# EE-Workshop.net
KiCad netlist of a schematic drawn in EAGLE
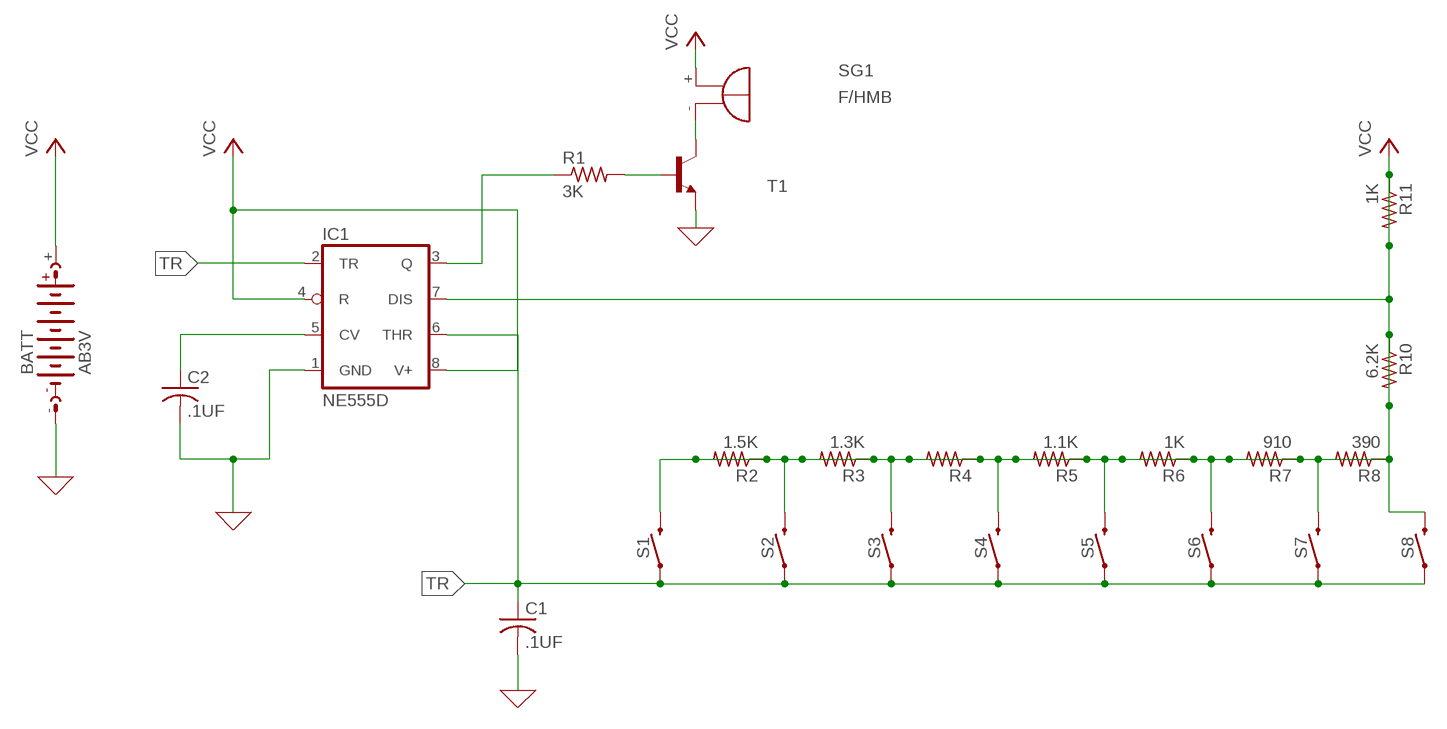
[diagram p0: schematic, sheet 1]

(export (version "E")
  (design (tool "Eeschema 10.0.6"))
  (components
    (comp (ref "BATT")
      (value "AB3V")
      (footprint "eagle-import:AB9V")
      (libsource (lib "eagle-import") (part "AB9V"))
    )
    (comp (ref "C1")
      (value ".1UF")
      (footprint "eagle-import:C0805")
      (libsource (lib "eagle-import") (part "C-USC0805"))
    )
    (comp (ref "C2")
      (value ".1UF")
      (footprint "eagle-import:C0805")
      (libsource (lib "eagle-import") (part "C-USC0805"))
    )
    (comp (ref "IC1")
      (value "NE555D")
      (footprint "eagle-import:SO08")
      (libsource (lib "eagle-import") (part "555DNE"))
    )
    (comp (ref "R1")
      (value "3K")
      (footprint "eagle-import:R0805")
      (libsource (lib "eagle-import") (part "R-US_R0805"))
    )
    (comp (ref "R2")
      (value "1.5K")
      (footprint "eagle-import:R0805")
      (libsource (lib "eagle-import") (part "R-US_R0805"))
    )
    (comp (ref "R3")
      (value "1.3K")
      (footprint "eagle-import:R0805")
      (libsource (lib "eagle-import") (part "R-US_R0805"))
    )
    (comp (ref "R4")
      (value "R-US_R0805")
      (footprint "eagle-import:R0805")
      (libsource (lib "eagle-import") (part "R-US_R0805"))
    )
    (comp (ref "R5")
      (value "1.1K")
      (footprint "eagle-import:R0805")
      (libsource (lib "eagle-import") (part "R-US_R0805"))
    )
    (comp (ref "R6")
      (value "1K")
      (footprint "eagle-import:R0805")
      (libsource (lib "eagle-import") (part "R-US_R0805"))
    )
    (comp (ref "R7")
      (value "910")
      (footprint "eagle-import:R0805")
      (libsource (lib "eagle-import") (part "R-US_R0805"))
    )
    (comp (ref "R8")
      (value "390")
      (footprint "eagle-import:R0805")
      (libsource (lib "eagle-import") (part "R-US_R0805"))
    )
    (comp (ref "R10")
      (value "6.2K")
      (footprint "eagle-import:R0805")
      (libsource (lib "eagle-import") (part "R-US_R0805"))
    )
    (comp (ref "R11")
      (value "1K")
      (footprint "eagle-import:R0805")
      (libsource (lib "eagle-import") (part "R-US_R0805"))
    )
    (comp (ref "S1")
      (value "MOMENTARY-SWITCH-SPST-SMD-6.2MM-TALL")
      (footprint "eagle-import:TACTILE_SWITCH_SMD_6.2MM_TALL")
      (libsource (lib "eagle-import") (part "MOMENTARY-SWITCH-SPST-SMD-6.2MM-TALL"))
    )
    (comp (ref "S2")
      (value "MOMENTARY-SWITCH-SPST-SMD-6.2MM-TALL")
      (footprint "eagle-import:TACTILE_SWITCH_SMD_6.2MM_TALL")
      (libsource (lib "eagle-import") (part "MOMENTARY-SWITCH-SPST-SMD-6.2MM-TALL"))
    )
    (comp (ref "S3")
      (value "MOMENTARY-SWITCH-SPST-SMD-6.2MM-TALL")
      (footprint "eagle-import:TACTILE_SWITCH_SMD_6.2MM_TALL")
      (libsource (lib "eagle-import") (part "MOMENTARY-SWITCH-SPST-SMD-6.2MM-TALL"))
    )
    (comp (ref "S4")
      (value "MOMENTARY-SWITCH-SPST-SMD-6.2MM-TALL")
      (footprint "eagle-import:TACTILE_SWITCH_SMD_6.2MM_TALL")
      (libsource (lib "eagle-import") (part "MOMENTARY-SWITCH-SPST-SMD-6.2MM-TALL"))
    )
    (comp (ref "S5")
      (value "MOMENTARY-SWITCH-SPST-SMD-6.2MM-TALL")
      (footprint "eagle-import:TACTILE_SWITCH_SMD_6.2MM_TALL")
      (libsource (lib "eagle-import") (part "MOMENTARY-SWITCH-SPST-SMD-6.2MM-TALL"))
    )
    (comp (ref "S6")
      (value "MOMENTARY-SWITCH-SPST-SMD-6.2MM-TALL")
      (footprint "eagle-import:TACTILE_SWITCH_SMD_6.2MM_TALL")
      (libsource (lib "eagle-import") (part "MOMENTARY-SWITCH-SPST-SMD-6.2MM-TALL"))
    )
    (comp (ref "S7")
      (value "MOMENTARY-SWITCH-SPST-SMD-6.2MM-TALL")
      (footprint "eagle-import:TACTILE_SWITCH_SMD_6.2MM_TALL")
      (libsource (lib "eagle-import") (part "MOMENTARY-SWITCH-SPST-SMD-6.2MM-TALL"))
    )
    (comp (ref "S8")
      (value "MOMENTARY-SWITCH-SPST-SMD-6.2MM-TALL")
      (footprint "eagle-import:TACTILE_SWITCH_SMD_6.2MM_TALL")
      (libsource (lib "eagle-import") (part "MOMENTARY-SWITCH-SPST-SMD-6.2MM-TALL"))
    )
    (comp (ref "SG1")
      (value "F/HMB")
      (footprint "eagle-import:F_HMB")
      (libsource (lib "eagle-import") (part "F/HMB"))
    )
    (comp (ref "T1")
      (value "BCW60-NPN-SOT23-BEC")
      (footprint "eagle-import:SOT23-BEC")
      (libsource (lib "eagle-import") (part "-NPN-SOT23-BECBCW60"))
    )
  )
  (nets
    (net (code "1") (name "GND") (class "Default")
      (node (ref "BATT") (pin "-") (pinfunction "-_-") (pintype "passive"))
      (node (ref "C1") (pin "2") (pinfunction "2_2") (pintype "passive"))
      (node (ref "C2") (pin "2") (pinfunction "2_2") (pintype "passive"))
      (node (ref "IC1") (pin "1") (pinfunction "GND_1") (pintype "power_in"))
      (node (ref "T1") (pin "E") (pinfunction "E_E") (pintype "passive"))
    )
    (net (code "2") (name "Net-(IC1-CV)") (class "Default")
      (node (ref "C2") (pin "1") (pinfunction "1_1") (pintype "passive"))
      (node (ref "IC1") (pin "5") (pinfunction "CV_5") (pintype "input"))
    )
    (net (code "3") (name "Net-(IC1-Q)") (class "Default")
      (node (ref "IC1") (pin "3") (pinfunction "Q_3") (pintype "output"))
      (node (ref "R1") (pin "1") (pinfunction "1_1") (pintype "passive"))
    )
    (net (code "4") (name "Net-(R1-Pad2)") (class "Default")
      (node (ref "R1") (pin "2") (pinfunction "2_2") (pintype "passive"))
      (node (ref "T1") (pin "B") (pinfunction "B_B") (pintype "passive"))
    )
    (net (code "5") (name "Net-(SG1-Pad-)") (class "Default")
      (node (ref "SG1") (pin "-") (pinfunction "-_-") (pintype "passive"))
      (node (ref "T1") (pin "C") (pinfunction "C_C") (pintype "passive"))
    )
    (net (code "6") (name "TR") (class "Default")
      (node (ref "C1") (pin "1") (pinfunction "1_1") (pintype "passive"))
      (node (ref "IC1") (pin "2") (pinfunction "TR_2") (pintype "input"))
      (node (ref "IC1") (pin "6") (pinfunction "THR_6") (pintype "input"))
      (node (ref "S1") (pin "A2") (pinfunction "1_A2") (pintype "passive"))
      (node (ref "S2") (pin "A2") (pinfunction "1_A2") (pintype "passive"))
      (node (ref "S3") (pin "A2") (pinfunction "1_A2") (pintype "passive"))
      (node (ref "S4") (pin "A2") (pinfunction "1_A2") (pintype "passive"))
      (node (ref "S5") (pin "A2") (pinfunction "1_A2") (pintype "passive"))
      (node (ref "S6") (pin "A2") (pinfunction "1_A2") (pintype "passive"))
      (node (ref "S7") (pin "A2") (pinfunction "1_A2") (pintype "passive"))
      (node (ref "S8") (pin "A2") (pinfunction "1_A2") (pintype "passive"))
    )
    (net (code "7") (name "VCC") (class "Default")
      (node (ref "BATT") (pin "+") (pinfunction "+_+") (pintype "passive"))
      (node (ref "IC1") (pin "4") (pinfunction "R_4") (pintype "input"))
      (node (ref "IC1") (pin "7") (pinfunction "DIS_7") (pintype "input"))
      (node (ref "IC1") (pin "8") (pinfunction "V+_8") (pintype "power_in"))
      (node (ref "R10") (pin "1") (pinfunction "1_1") (pintype "passive"))
      (node (ref "R10") (pin "2") (pinfunction "2_2") (pintype "passive"))
      (node (ref "R11") (pin "1") (pinfunction "1_1") (pintype "passive"))
      (node (ref "R11") (pin "2") (pinfunction "2_2") (pintype "passive"))
      (node (ref "R2") (pin "1") (pinfunction "1_1") (pintype "passive"))
      (node (ref "R2") (pin "2") (pinfunction "2_2") (pintype "passive"))
      (node (ref "R3") (pin "1") (pinfunction "1_1") (pintype "passive"))
      (node (ref "R3") (pin "2") (pinfunction "2_2") (pintype "passive"))
      (node (ref "R4") (pin "1") (pinfunction "1_1") (pintype "passive"))
      (node (ref "R4") (pin "2") (pinfunction "2_2") (pintype "passive"))
      (node (ref "R5") (pin "1") (pinfunction "1_1") (pintype "passive"))
      (node (ref "R5") (pin "2") (pinfunction "2_2") (pintype "passive"))
      (node (ref "R6") (pin "1") (pinfunction "1_1") (pintype "passive"))
      (node (ref "R6") (pin "2") (pinfunction "2_2") (pintype "passive"))
      (node (ref "R7") (pin "1") (pinfunction "1_1") (pintype "passive"))
      (node (ref "R7") (pin "2") (pinfunction "2_2") (pintype "passive"))
      (node (ref "R8") (pin "1") (pinfunction "1_1") (pintype "passive"))
      (node (ref "R8") (pin "2") (pinfunction "2_2") (pintype "passive"))
      (node (ref "S1") (pin "B2") (pinfunction "2_B2") (pintype "passive"))
      (node (ref "S2") (pin "B2") (pinfunction "2_B2") (pintype "passive"))
      (node (ref "S3") (pin "B2") (pinfunction "2_B2") (pintype "passive"))
      (node (ref "S4") (pin "B2") (pinfunction "2_B2") (pintype "passive"))
      (node (ref "S5") (pin "B2") (pinfunction "2_B2") (pintype "passive"))
      (node (ref "S6") (pin "B2") (pinfunction "2_B2") (pintype "passive"))
      (node (ref "S7") (pin "B2") (pinfunction "2_B2") (pintype "passive"))
      (node (ref "S8") (pin "B2") (pinfunction "2_B2") (pintype "passive"))
      (node (ref "SG1") (pin "+") (pinfunction "+_+") (pintype "passive"))
    )
  )
)
